# dram.net
KiCad netlist of a schematic drawn in Altium Designer
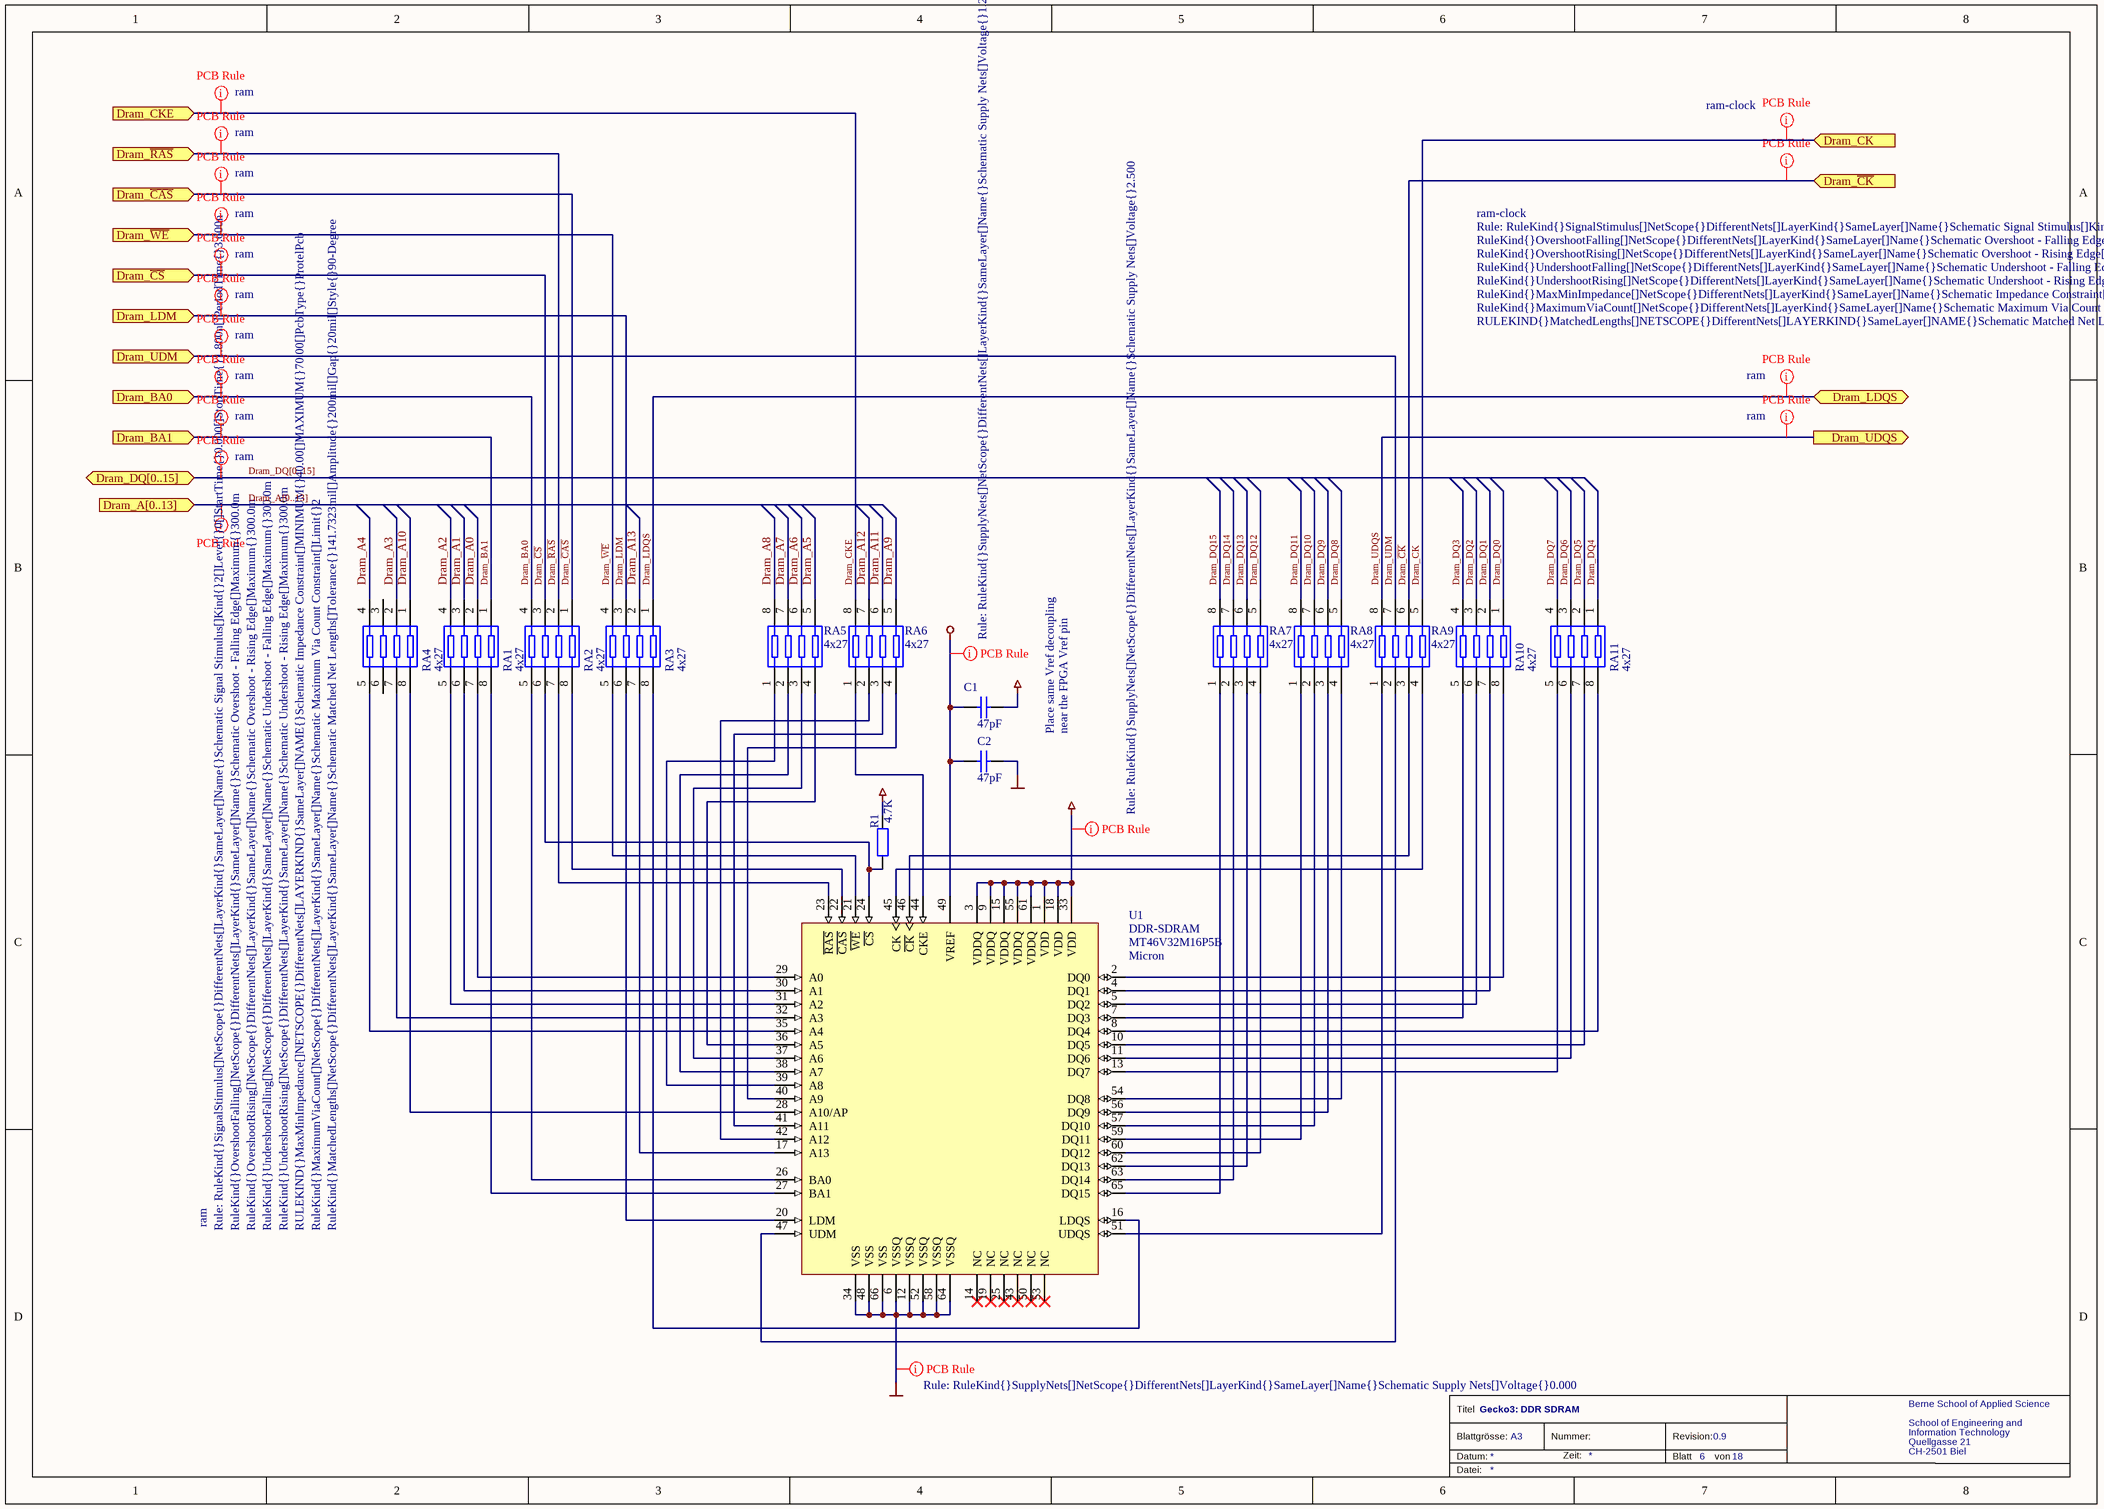
[diagram p0: dram.SCHDOC]

(export (version "E")
  (design (tool "Eeschema 10.0.6"))
  (components
    (comp (ref "C1")
      (value "47pF")
      (footprint "0402")
      (description "Capacitor")
      (fields
        (field (name "MANUFACTURER") "Murata")
        (field (name "PART NUMBER") "GRM1555C1H470JZ01D")
        (field (name "PUBLISHER") "Altium Limited")
      )
      (libsource (lib "Miscellaneous Devices") (part "Cap"))
    )
    (comp (ref "C2")
      (value "47pF")
      (footprint "0402")
      (description "Capacitor")
      (fields
        (field (name "MANUFACTURER") "Murata")
        (field (name "PART NUMBER") "GRM1555C1H470JZ01D")
        (field (name "PUBLISHER") "Altium Limited")
      )
      (libsource (lib "Miscellaneous Devices") (part "Cap"))
    )
    (comp (ref "R1")
      (value "4.7K")
      (footprint "0402")
      (description "Resistor")
      (fields
        (field (name "MANUFACTURER") "PHYCOMP")
        (field (name "PART NUMBER") "232270674702")
        (field (name "PUBLISHER") "Altium Limited")
      )
      (libsource (lib "Miscellaneous Devices") (part "Res2"))
    )
    (comp (ref "RA1")
      (value "4x27")
      (footprint "1206_ARRAY")
      (fields (field (name "MANUFACTURER") "PHYCOMP") (field (name "PART NUMBER") "235003410279"))
      (libsource (lib "CoolARM-Kit") (part "R_ARRAY_4_SMD"))
    )
    (comp (ref "RA2")
      (value "4x27")
      (footprint "1206_ARRAY")
      (fields (field (name "MANUFACTURER") "PHYCOMP") (field (name "PART NUMBER") "235003410279"))
      (libsource (lib "CoolARM-Kit") (part "R_ARRAY_4_SMD"))
    )
    (comp (ref "RA3")
      (value "4x27")
      (footprint "1206_ARRAY")
      (fields (field (name "MANUFACTURER") "PHYCOMP") (field (name "PART NUMBER") "235003410279"))
      (libsource (lib "CoolARM-Kit") (part "R_ARRAY_4_SMD"))
    )
    (comp (ref "RA4")
      (value "4x27")
      (footprint "1206_ARRAY")
      (fields (field (name "MANUFACTURER") "PHYCOMP") (field (name "PART NUMBER") "235003410279"))
      (libsource (lib "CoolARM-Kit") (part "R_ARRAY_4_SMD"))
    )
    (comp (ref "RA5")
      (value "4x27")
      (footprint "1206_ARRAY")
      (fields (field (name "MANUFACTURER") "PHYCOMP") (field (name "PART NUMBER") "235003410279"))
      (libsource (lib "CoolARM-Kit") (part "R_ARRAY_4_SMD"))
    )
    (comp (ref "RA6")
      (value "4x27")
      (footprint "1206_ARRAY")
      (fields (field (name "MANUFACTURER") "PHYCOMP") (field (name "PART NUMBER") "235003410279"))
      (libsource (lib "CoolARM-Kit") (part "R_ARRAY_4_SMD"))
    )
    (comp (ref "RA7")
      (value "4x27")
      (footprint "1206_ARRAY")
      (fields (field (name "MANUFACTURER") "PHYCOMP") (field (name "PART NUMBER") "235003410279"))
      (libsource (lib "CoolARM-Kit") (part "R_ARRAY_4_SMD"))
    )
    (comp (ref "RA8")
      (value "4x27")
      (footprint "1206_ARRAY")
      (fields (field (name "MANUFACTURER") "PHYCOMP") (field (name "PART NUMBER") "235003410279"))
      (libsource (lib "CoolARM-Kit") (part "R_ARRAY_4_SMD"))
    )
    (comp (ref "RA9")
      (value "4x27")
      (footprint "1206_ARRAY")
      (fields (field (name "MANUFACTURER") "PHYCOMP") (field (name "PART NUMBER") "235003410279"))
      (libsource (lib "CoolARM-Kit") (part "R_ARRAY_4_SMD"))
    )
    (comp (ref "RA10")
      (value "4x27")
      (footprint "1206_ARRAY")
      (fields (field (name "MANUFACTURER") "PHYCOMP") (field (name "PART NUMBER") "235003410279"))
      (libsource (lib "CoolARM-Kit") (part "R_ARRAY_4_SMD"))
    )
    (comp (ref "RA11")
      (value "4x27")
      (footprint "1206_ARRAY")
      (fields (field (name "MANUFACTURER") "PHYCOMP") (field (name "PART NUMBER") "235003410279"))
      (libsource (lib "CoolARM-Kit") (part "R_ARRAY_4_SMD"))
    )
    (comp (ref "U1")
      (value "DDR-SDRAM")
      (footprint "TSOP66")
      (description "general model for ddr sdram's")
      (fields
        (field (name "ALTIUM_VALUE") "MT46V32M16P5B")
        (field (name "VENDOR") "Micron")
        (field (name "MANUFACTURER") "Micron")
        (field (name "PART NUMBER") "MT46V32M16P5B")
      )
      (libsource (lib "gecko3-user") (part "DDR-SDRAM"))
    )
  )
  (nets
    (net (code "1") (name "/Dram_A0") (class "Default")
      (node (ref "RA1") (pin "2") (pinfunction "2_2") (pintype "passive"))
    )
    (net (code "2") (name "/Dram_A1") (class "Default")
      (node (ref "RA1") (pin "3") (pinfunction "3_3") (pintype "passive"))
    )
    (net (code "3") (name "/Dram_A2") (class "Default")
      (node (ref "RA1") (pin "4") (pinfunction "4_4") (pintype "passive"))
    )
    (net (code "4") (name "/Dram_A3") (class "Default")
      (node (ref "RA4") (pin "2") (pinfunction "2_2") (pintype "passive"))
    )
    (net (code "5") (name "/Dram_A4") (class "Default")
      (node (ref "RA4") (pin "4") (pinfunction "4_4") (pintype "passive"))
    )
    (net (code "6") (name "/Dram_A5") (class "Default")
      (node (ref "RA5") (pin "5") (pinfunction "5_5") (pintype "passive"))
    )
    (net (code "7") (name "/Dram_A6") (class "Default")
      (node (ref "RA5") (pin "6") (pinfunction "6_6") (pintype "passive"))
    )
    (net (code "8") (name "/Dram_A7") (class "Default")
      (node (ref "RA5") (pin "7") (pinfunction "7_7") (pintype "passive"))
    )
    (net (code "9") (name "/Dram_A8") (class "Default")
      (node (ref "RA5") (pin "8") (pinfunction "8_8") (pintype "passive"))
    )
    (net (code "10") (name "/Dram_A9") (class "Default")
      (node (ref "RA6") (pin "5") (pinfunction "5_5") (pintype "passive"))
    )
    (net (code "11") (name "/Dram_A10") (class "Default")
      (node (ref "RA4") (pin "1") (pinfunction "1_1") (pintype "passive"))
    )
    (net (code "12") (name "/Dram_A11") (class "Default")
      (node (ref "RA6") (pin "6") (pinfunction "6_6") (pintype "passive"))
    )
    (net (code "13") (name "/Dram_A12") (class "Default")
      (node (ref "RA6") (pin "7") (pinfunction "7_7") (pintype "passive"))
    )
    (net (code "14") (name "/Dram_A13") (class "Default")
      (node (ref "RA3") (pin "2") (pinfunction "2_2") (pintype "passive"))
    )
    (net (code "16") (name "/Dram_BA0") (class "Default")
      (node (ref "RA2") (pin "4") (pinfunction "4_4") (pintype "passive"))
    )
    (net (code "17") (name "/Dram_BA1") (class "Default")
      (node (ref "RA1") (pin "1") (pinfunction "1_1") (pintype "passive"))
    )
    (net (code "18") (name "/Dram_CK") (class "Default")
      (node (ref "RA9") (pin "5") (pinfunction "5_5") (pintype "passive"))
    )
    (net (code "19") (name "/Dram_CKE") (class "Default")
      (node (ref "RA6") (pin "8") (pinfunction "8_8") (pintype "passive"))
    )
    (net (code "20") (name "/Dram_DQ0") (class "Default")
      (node (ref "RA10") (pin "1") (pinfunction "1_1") (pintype "passive"))
    )
    (net (code "21") (name "/Dram_DQ1") (class "Default")
      (node (ref "RA10") (pin "2") (pinfunction "2_2") (pintype "passive"))
    )
    (net (code "22") (name "/Dram_DQ2") (class "Default")
      (node (ref "RA10") (pin "3") (pinfunction "3_3") (pintype "passive"))
    )
    (net (code "23") (name "/Dram_DQ3") (class "Default")
      (node (ref "RA10") (pin "4") (pinfunction "4_4") (pintype "passive"))
    )
    (net (code "24") (name "/Dram_DQ4") (class "Default")
      (node (ref "RA11") (pin "1") (pinfunction "1_1") (pintype "passive"))
    )
    (net (code "25") (name "/Dram_DQ5") (class "Default")
      (node (ref "RA11") (pin "2") (pinfunction "2_2") (pintype "passive"))
    )
    (net (code "26") (name "/Dram_DQ6") (class "Default")
      (node (ref "RA11") (pin "3") (pinfunction "3_3") (pintype "passive"))
    )
    (net (code "27") (name "/Dram_DQ7") (class "Default")
      (node (ref "RA11") (pin "4") (pinfunction "4_4") (pintype "passive"))
    )
    (net (code "28") (name "/Dram_DQ8") (class "Default")
      (node (ref "RA8") (pin "5") (pinfunction "5_5") (pintype "passive"))
    )
    (net (code "29") (name "/Dram_DQ9") (class "Default")
      (node (ref "RA8") (pin "6") (pinfunction "6_6") (pintype "passive"))
    )
    (net (code "30") (name "/Dram_DQ10") (class "Default")
      (node (ref "RA8") (pin "7") (pinfunction "7_7") (pintype "passive"))
    )
    (net (code "31") (name "/Dram_DQ11") (class "Default")
      (node (ref "RA8") (pin "8") (pinfunction "8_8") (pintype "passive"))
    )
    (net (code "32") (name "/Dram_DQ12") (class "Default")
      (node (ref "RA7") (pin "5") (pinfunction "5_5") (pintype "passive"))
    )
    (net (code "33") (name "/Dram_DQ13") (class "Default")
      (node (ref "RA7") (pin "6") (pinfunction "6_6") (pintype "passive"))
    )
    (net (code "34") (name "/Dram_DQ14") (class "Default")
      (node (ref "RA7") (pin "7") (pinfunction "7_7") (pintype "passive"))
    )
    (net (code "35") (name "/Dram_DQ15") (class "Default")
      (node (ref "RA7") (pin "8") (pinfunction "8_8") (pintype "passive"))
    )
    (net (code "37") (name "/Dram_LDM") (class "Default")
      (node (ref "RA3") (pin "3") (pinfunction "3_3") (pintype "passive"))
    )
    (net (code "38") (name "/Dram_LDQS") (class "Default")
      (node (ref "RA3") (pin "1") (pinfunction "1_1") (pintype "passive"))
    )
    (net (code "39") (name "/Dram_UDM") (class "Default")
      (node (ref "RA9") (pin "7") (pinfunction "7_7") (pintype "passive"))
    )
    (net (code "40") (name "/Dram_UDQS") (class "Default")
      (node (ref "RA9") (pin "8") (pinfunction "8_8") (pintype "passive"))
    )
    (net (code "41") (name "/Dram_~{CAS}") (class "Default")
      (node (ref "RA2") (pin "1") (pinfunction "1_1") (pintype "passive"))
    )
    (net (code "42") (name "/Dram_~{CK}") (class "Default")
      (node (ref "RA9") (pin "6") (pinfunction "6_6") (pintype "passive"))
    )
    (net (code "43") (name "/Dram_~{CS}") (class "Default")
      (node (ref "RA2") (pin "3") (pinfunction "3_3") (pintype "passive"))
    )
    (net (code "44") (name "/Dram_~{RAS}") (class "Default")
      (node (ref "RA2") (pin "2") (pinfunction "2_2") (pintype "passive"))
    )
    (net (code "45") (name "/Dram_~{WE}") (class "Default")
      (node (ref "RA3") (pin "4") (pinfunction "4_4") (pintype "passive"))
    )
    (net (code "46") (name "2.5V") (class "Default")
      (node (ref "C1") (pin "1") (pinfunction "1_1") (pintype "passive"))
      (node (ref "R1") (pin "2") (pinfunction "2_2") (pintype "passive"))
      (node (ref "U1") (pin "1") (pinfunction "VDD_1") (pintype "power_in"))
      (node (ref "U1") (pin "15") (pinfunction "VDDQ_15") (pintype "power_in"))
      (node (ref "U1") (pin "18") (pinfunction "VDD_18") (pintype "power_in"))
      (node (ref "U1") (pin "3") (pinfunction "VDDQ_3") (pintype "power_in"))
      (node (ref "U1") (pin "33") (pinfunction "VDD_33") (pintype "power_in"))
      (node (ref "U1") (pin "55") (pinfunction "VDDQ_55") (pintype "power_in"))
      (node (ref "U1") (pin "61") (pinfunction "VDDQ_61") (pintype "power_in"))
      (node (ref "U1") (pin "9") (pinfunction "VDDQ_9") (pintype "power_in"))
    )
    (net (code "47") (name "GND") (class "Default")
      (node (ref "C2") (pin "1") (pinfunction "1_1") (pintype "passive"))
      (node (ref "U1") (pin "12") (pinfunction "VSSQ_12") (pintype "power_in"))
      (node (ref "U1") (pin "34") (pinfunction "VSS_34") (pintype "power_in"))
      (node (ref "U1") (pin "48") (pinfunction "VSS_48") (pintype "power_in"))
      (node (ref "U1") (pin "52") (pinfunction "VSSQ_52") (pintype "power_in"))
      (node (ref "U1") (pin "58") (pinfunction "VSSQ_58") (pintype "power_in"))
      (node (ref "U1") (pin "6") (pinfunction "VSSQ_6") (pintype "power_in"))
      (node (ref "U1") (pin "64") (pinfunction "VSSQ_64") (pintype "power_in"))
      (node (ref "U1") (pin "66") (pinfunction "VSS_66") (pintype "power_in"))
    )
    (net (code "48") (name "Net-(U1-A0)") (class "Default")
      (node (ref "RA1") (pin "7") (pinfunction "7_7") (pintype "passive"))
      (node (ref "U1") (pin "29") (pinfunction "A0_29") (pintype "input"))
    )
    (net (code "49") (name "Net-(U1-A1)") (class "Default")
      (node (ref "RA1") (pin "6") (pinfunction "6_6") (pintype "passive"))
      (node (ref "U1") (pin "30") (pinfunction "A1_30") (pintype "input"))
    )
    (net (code "50") (name "Net-(U1-A2)") (class "Default")
      (node (ref "RA1") (pin "5") (pinfunction "5_5") (pintype "passive"))
      (node (ref "U1") (pin "31") (pinfunction "A2_31") (pintype "input"))
    )
    (net (code "51") (name "Net-(U1-A3)") (class "Default")
      (node (ref "RA4") (pin "7") (pinfunction "7_7") (pintype "passive"))
      (node (ref "U1") (pin "32") (pinfunction "A3_32") (pintype "input"))
    )
    (net (code "52") (name "Net-(U1-A4)") (class "Default")
      (node (ref "RA4") (pin "5") (pinfunction "5_5") (pintype "passive"))
      (node (ref "U1") (pin "35") (pinfunction "A4_35") (pintype "input"))
    )
    (net (code "53") (name "Net-(U1-A5)") (class "Default")
      (node (ref "RA5") (pin "4") (pinfunction "4_4") (pintype "passive"))
      (node (ref "U1") (pin "36") (pinfunction "A5_36") (pintype "input"))
    )
    (net (code "54") (name "Net-(U1-A6)") (class "Default")
      (node (ref "RA5") (pin "3") (pinfunction "3_3") (pintype "passive"))
      (node (ref "U1") (pin "37") (pinfunction "A6_37") (pintype "input"))
    )
    (net (code "55") (name "Net-(U1-A7)") (class "Default")
      (node (ref "RA5") (pin "2") (pinfunction "2_2") (pintype "passive"))
      (node (ref "U1") (pin "38") (pinfunction "A7_38") (pintype "input"))
    )
    (net (code "56") (name "Net-(U1-A8)") (class "Default")
      (node (ref "RA5") (pin "1") (pinfunction "1_1") (pintype "passive"))
      (node (ref "U1") (pin "39") (pinfunction "A8_39") (pintype "input"))
    )
    (net (code "57") (name "Net-(U1-A9)") (class "Default")
      (node (ref "RA6") (pin "4") (pinfunction "4_4") (pintype "passive"))
      (node (ref "U1") (pin "40") (pinfunction "A9_40") (pintype "input"))
    )
    (net (code "58") (name "Net-(U1-A10{slash}AP)") (class "Default")
      (node (ref "RA4") (pin "8") (pinfunction "8_8") (pintype "passive"))
      (node (ref "U1") (pin "28") (pinfunction "A10/AP_28") (pintype "input"))
    )
    (net (code "59") (name "Net-(U1-A11)") (class "Default")
      (node (ref "RA6") (pin "3") (pinfunction "3_3") (pintype "passive"))
      (node (ref "U1") (pin "41") (pinfunction "A11_41") (pintype "input"))
    )
    (net (code "60") (name "Net-(U1-A12)") (class "Default")
      (node (ref "RA6") (pin "2") (pinfunction "2_2") (pintype "passive"))
      (node (ref "U1") (pin "42") (pinfunction "A12_42") (pintype "input"))
    )
    (net (code "61") (name "Net-(U1-A13)") (class "Default")
      (node (ref "RA3") (pin "7") (pinfunction "7_7") (pintype "passive"))
      (node (ref "U1") (pin "17") (pinfunction "A13_17") (pintype "input"))
    )
    (net (code "62") (name "Net-(U1-BA0)") (class "Default")
      (node (ref "RA2") (pin "5") (pinfunction "5_5") (pintype "passive"))
      (node (ref "U1") (pin "26") (pinfunction "BA0_26") (pintype "input"))
    )
    (net (code "63") (name "Net-(U1-BA1)") (class "Default")
      (node (ref "RA1") (pin "8") (pinfunction "8_8") (pintype "passive"))
      (node (ref "U1") (pin "27") (pinfunction "BA1_27") (pintype "input"))
    )
    (net (code "64") (name "Net-(U1-CK)") (class "Default")
      (node (ref "RA9") (pin "4") (pinfunction "4_4") (pintype "passive"))
      (node (ref "U1") (pin "45") (pinfunction "CK_45") (pintype "input"))
    )
    (net (code "65") (name "Net-(U1-CKE)") (class "Default")
      (node (ref "RA6") (pin "1") (pinfunction "1_1") (pintype "passive"))
      (node (ref "U1") (pin "44") (pinfunction "CKE_44") (pintype "input"))
    )
    (net (code "66") (name "Net-(U1-DQ0)") (class "Default")
      (node (ref "RA10") (pin "8") (pinfunction "8_8") (pintype "passive"))
      (node (ref "U1") (pin "2") (pinfunction "DQ0_2") (pintype "bidirectional"))
    )
    (net (code "67") (name "Net-(U1-DQ1)") (class "Default")
      (node (ref "RA10") (pin "7") (pinfunction "7_7") (pintype "passive"))
      (node (ref "U1") (pin "4") (pinfunction "DQ1_4") (pintype "bidirectional"))
    )
    (net (code "68") (name "Net-(U1-DQ2)") (class "Default")
      (node (ref "RA10") (pin "6") (pinfunction "6_6") (pintype "passive"))
      (node (ref "U1") (pin "5") (pinfunction "DQ2_5") (pintype "bidirectional"))
    )
    (net (code "69") (name "Net-(U1-DQ3)") (class "Default")
      (node (ref "RA10") (pin "5") (pinfunction "5_5") (pintype "passive"))
      (node (ref "U1") (pin "7") (pinfunction "DQ3_7") (pintype "bidirectional"))
    )
    (net (code "70") (name "Net-(U1-DQ4)") (class "Default")
      (node (ref "RA11") (pin "8") (pinfunction "8_8") (pintype "passive"))
      (node (ref "U1") (pin "8") (pinfunction "DQ4_8") (pintype "bidirectional"))
    )
    (net (code "71") (name "Net-(U1-DQ5)") (class "Default")
      (node (ref "RA11") (pin "7") (pinfunction "7_7") (pintype "passive"))
      (node (ref "U1") (pin "10") (pinfunction "DQ5_10") (pintype "bidirectional"))
    )
    (net (code "72") (name "Net-(U1-DQ6)") (class "Default")
      (node (ref "RA11") (pin "6") (pinfunction "6_6") (pintype "passive"))
      (node (ref "U1") (pin "11") (pinfunction "DQ6_11") (pintype "bidirectional"))
    )
    (net (code "73") (name "Net-(U1-DQ7)") (class "Default")
      (node (ref "RA11") (pin "5") (pinfunction "5_5") (pintype "passive"))
      (node (ref "U1") (pin "13") (pinfunction "DQ7_13") (pintype "bidirectional"))
    )
    (net (code "74") (name "Net-(U1-DQ8)") (class "Default")
      (node (ref "RA8") (pin "4") (pinfunction "4_4") (pintype "passive"))
      (node (ref "U1") (pin "54") (pinfunction "DQ8_54") (pintype "bidirectional"))
    )
    (net (code "75") (name "Net-(U1-DQ9)") (class "Default")
      (node (ref "RA8") (pin "3") (pinfunction "3_3") (pintype "passive"))
      (node (ref "U1") (pin "56") (pinfunction "DQ9_56") (pintype "bidirectional"))
    )
    (net (code "76") (name "Net-(U1-DQ10)") (class "Default")
      (node (ref "RA8") (pin "2") (pinfunction "2_2") (pintype "passive"))
      (node (ref "U1") (pin "57") (pinfunction "DQ10_57") (pintype "bidirectional"))
    )
    (net (code "77") (name "Net-(U1-DQ11)") (class "Default")
      (node (ref "RA8") (pin "1") (pinfunction "1_1") (pintype "passive"))
      (node (ref "U1") (pin "59") (pinfunction "DQ11_59") (pintype "bidirectional"))
    )
    (net (code "78") (name "Net-(U1-DQ12)") (class "Default")
      (node (ref "RA7") (pin "4") (pinfunction "4_4") (pintype "passive"))
      (node (ref "U1") (pin "60") (pinfunction "DQ12_60") (pintype "bidirectional"))
    )
    (net (code "79") (name "Net-(U1-DQ13)") (class "Default")
      (node (ref "RA7") (pin "3") (pinfunction "3_3") (pintype "passive"))
      (node (ref "U1") (pin "62") (pinfunction "DQ13_62") (pintype "bidirectional"))
    )
    (net (code "80") (name "Net-(U1-DQ14)") (class "Default")
      (node (ref "RA7") (pin "2") (pinfunction "2_2") (pintype "passive"))
      (node (ref "U1") (pin "63") (pinfunction "DQ14_63") (pintype "bidirectional"))
    )
    (net (code "81") (name "Net-(U1-DQ15)") (class "Default")
      (node (ref "RA7") (pin "1") (pinfunction "1_1") (pintype "passive"))
      (node (ref "U1") (pin "65") (pinfunction "DQ15_65") (pintype "bidirectional"))
    )
    (net (code "82") (name "Net-(U1-LDM)") (class "Default")
      (node (ref "RA3") (pin "6") (pinfunction "6_6") (pintype "passive"))
      (node (ref "U1") (pin "20") (pinfunction "LDM_20") (pintype "input"))
    )
    (net (code "83") (name "Net-(U1-LDQS)") (class "Default")
      (node (ref "RA3") (pin "8") (pinfunction "8_8") (pintype "passive"))
      (node (ref "U1") (pin "16") (pinfunction "LDQS_16") (pintype "bidirectional"))
    )
    (net (code "84") (name "Net-(U1-UDM)") (class "Default")
      (node (ref "RA9") (pin "2") (pinfunction "2_2") (pintype "passive"))
      (node (ref "U1") (pin "47") (pinfunction "UDM_47") (pintype "input"))
    )
    (net (code "85") (name "Net-(U1-UDQS)") (class "Default")
      (node (ref "RA9") (pin "1") (pinfunction "1_1") (pintype "passive"))
      (node (ref "U1") (pin "51") (pinfunction "UDQS_51") (pintype "bidirectional"))
    )
    (net (code "86") (name "Net-(U1-~{CAS})") (class "Default")
      (node (ref "RA2") (pin "8") (pinfunction "8_8") (pintype "passive"))
      (node (ref "U1") (pin "22") (pinfunction "~{CAS}_22") (pintype "input"))
    )
    (net (code "87") (name "Net-(U1-~{CK})") (class "Default")
      (node (ref "RA9") (pin "3") (pinfunction "3_3") (pintype "passive"))
      (node (ref "U1") (pin "46") (pinfunction "~{CK}_46") (pintype "input"))
    )
    (net (code "88") (name "Net-(U1-~{CS})") (class "Default")
      (node (ref "R1") (pin "1") (pinfunction "1_1") (pintype "passive"))
      (node (ref "RA2") (pin "6") (pinfunction "6_6") (pintype "passive"))
      (node (ref "U1") (pin "24") (pinfunction "~{CS}_24") (pintype "input"))
    )
    (net (code "89") (name "Net-(U1-~{RAS})") (class "Default")
      (node (ref "RA2") (pin "7") (pinfunction "7_7") (pintype "passive"))
      (node (ref "U1") (pin "23") (pinfunction "~{RAS}_23") (pintype "input"))
    )
    (net (code "90") (name "Net-(U1-~{WE})") (class "Default")
      (node (ref "RA3") (pin "5") (pinfunction "5_5") (pintype "passive"))
      (node (ref "U1") (pin "21") (pinfunction "~{WE}_21") (pintype "input"))
    )
    (net (code "91") (name "Vref") (class "Default")
      (node (ref "C1") (pin "2") (pinfunction "2_2") (pintype "passive"))
      (node (ref "C2") (pin "2") (pinfunction "2_2") (pintype "passive"))
      (node (ref "U1") (pin "49") (pinfunction "VREF_49") (pintype "power_in"))
    )
    (net (code "92") (name "unconnected-(RA4-Pad3)") (class "Default")
      (node (ref "RA4") (pin "3") (pinfunction "3_3") (pintype "passive"))
    )
    (net (code "93") (name "unconnected-(RA4-Pad6)") (class "Default")
      (node (ref "RA4") (pin "6") (pinfunction "6_6") (pintype "passive"))
    )
    (net (code "94") (name "unconnected-(U1-NC-Pad14)") (class "Default")
      (node (ref "U1") (pin "14") (pinfunction "NC_14") (pintype "passive+no_connect"))
    )
    (net (code "95") (name "unconnected-(U1-NC-Pad19)") (class "Default")
      (node (ref "U1") (pin "19") (pinfunction "NC_19") (pintype "passive+no_connect"))
    )
    (net (code "96") (name "unconnected-(U1-NC-Pad25)") (class "Default")
      (node (ref "U1") (pin "25") (pinfunction "NC_25") (pintype "passive+no_connect"))
    )
    (net (code "97") (name "unconnected-(U1-NC-Pad43)") (class "Default")
      (node (ref "U1") (pin "43") (pinfunction "NC_43") (pintype "passive+no_connect"))
    )
    (net (code "98") (name "unconnected-(U1-NC-Pad50)") (class "Default")
      (node (ref "U1") (pin "50") (pinfunction "NC_50") (pintype "passive+no_connect"))
    )
    (net (code "99") (name "unconnected-(U1-NC-Pad53)") (class "Default")
      (node (ref "U1") (pin "53") (pinfunction "NC_53") (pintype "passive+no_connect"))
    )
  )
)
